# micADM510.net
KiCad netlist of a schematic drawn in EAGLE
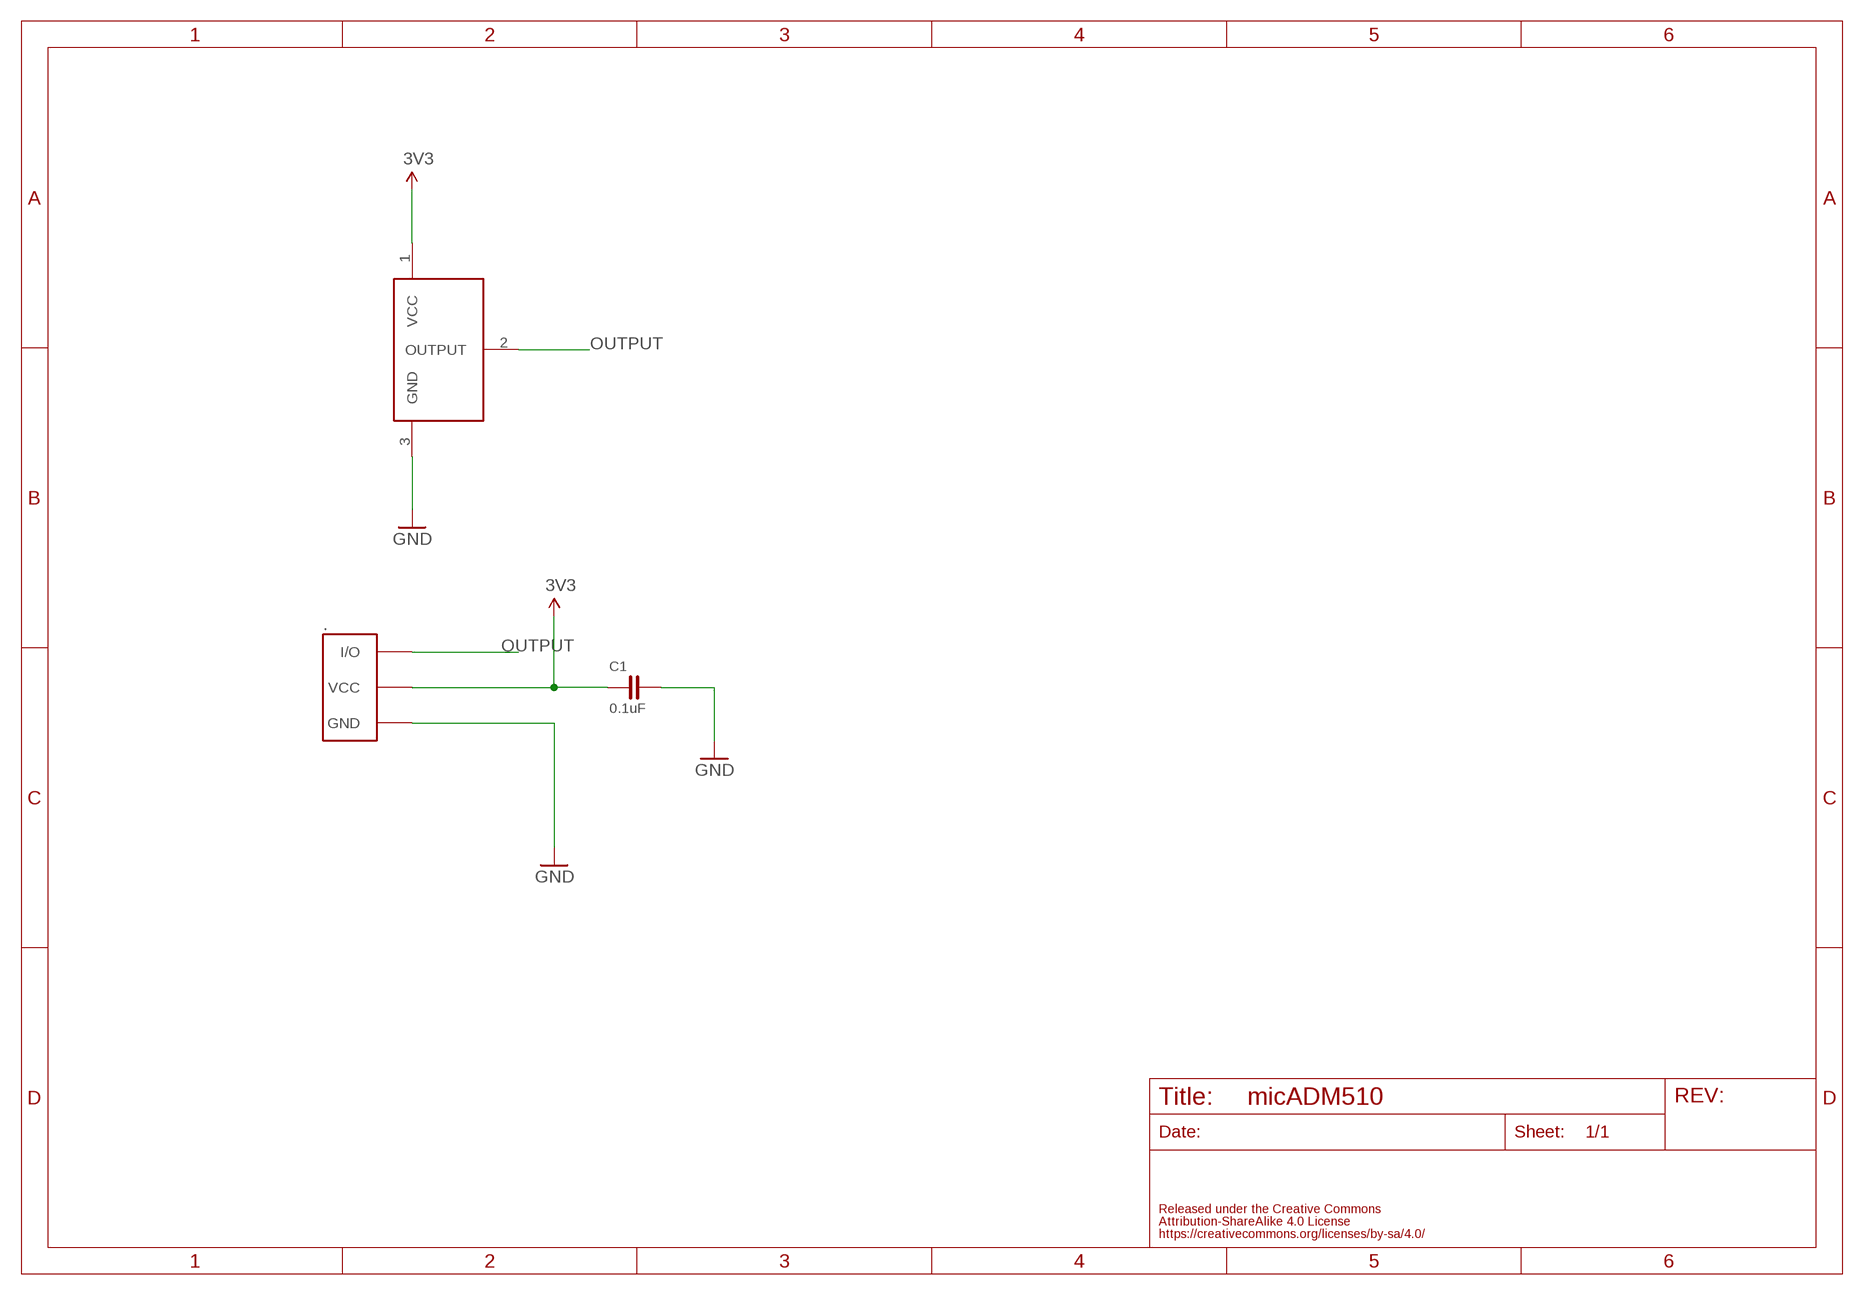
[diagram p0: schematic, sheet 1]

(export (version "E")
  (design (tool "Eeschema 10.0.6"))
  (components
    (comp (ref ".")
      (value "FABO_BRICK_3PIN-S03B-PASK-2")
      (footprint "eagle-import:FABO_BRICK_3PIN_S03B-PASK-2")
      (libsource (lib "eagle-import") (part "FABO_BRICK_3PIN-S03B-PASK-2"))
    )
    (comp (ref "ADM510")
      (value "ANALOG-MICADMP510")
      (footprint "eagle-import:INVERSENSE-ADMP510")
      (libsource (lib "eagle-import") (part "ANALOG-MICADMP510"))
    )
    (comp (ref "C1")
      (value "0.1uF")
      (footprint "eagle-import:0603")
      (libsource (lib "eagle-import") (part "CAPACITOR-0603"))
    )
  )
  (nets
    (net (code "1") (name "/OUTPUT") (class "Default")
      (node (ref ".") (pin "I/O") (pinfunction "I/O_I/O") (pintype "bidirectional"))
      (node (ref "ADM510") (pin "2") (pinfunction "OUTPUT_2") (pintype "bidirectional"))
    )
    (net (code "2") (name "3V3") (class "Default")
      (node (ref ".") (pin "VCC") (pinfunction "VCC_VCC") (pintype "bidirectional"))
      (node (ref "ADM510") (pin "1") (pinfunction "VCC_1") (pintype "bidirectional"))
      (node (ref "C1") (pin "1") (pinfunction "1_1") (pintype "passive"))
    )
    (net (code "3") (name "GND") (class "Default")
      (node (ref ".") (pin "GND") (pinfunction "GND_GND") (pintype "bidirectional"))
      (node (ref "ADM510") (pin "3") (pinfunction "GND_3") (pintype "bidirectional"))
      (node (ref "C1") (pin "2") (pinfunction "2_2") (pintype "passive"))
    )
  )
)
